# controller.net
KiCad netlist of a schematic drawn in EAGLE
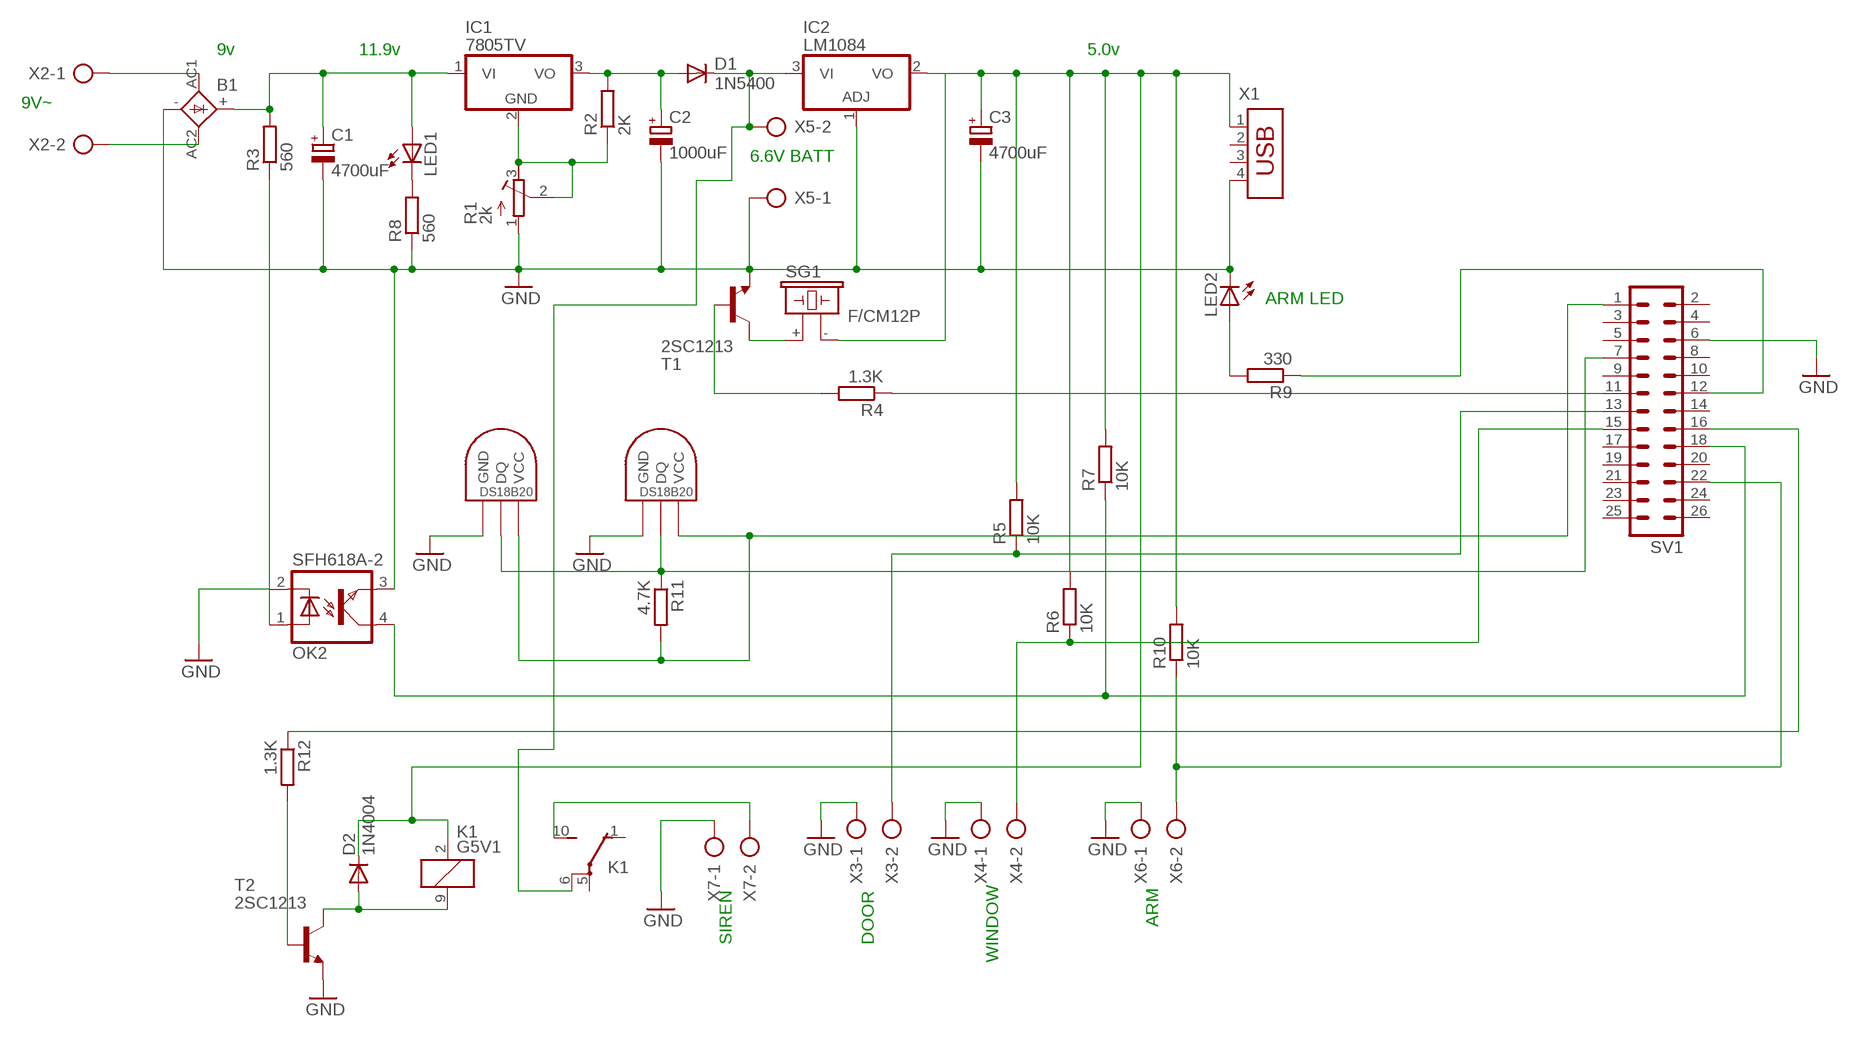
[diagram p0: schematic, sheet 1]

(export (version "E")
  (design (tool "Eeschema 10.0.6"))
  (components
    (comp (ref "B1")
      (value "S41")
      (footprint "eagle-import:S41")
      (libsource (lib "eagle-import") (part "S41"))
    )
    (comp (ref "C1")
      (value "4700uF")
      (footprint "eagle-import:E5-13")
      (libsource (lib "eagle-import") (part "CPOL-EUE5-13"))
    )
    (comp (ref "C2")
      (value "1000uF")
      (footprint "eagle-import:E5-10,5")
      (libsource (lib "eagle-import") (part "CPOL-EUE5-10.5"))
    )
    (comp (ref "C3")
      (value "4700uF")
      (footprint "eagle-import:E5-13")
      (libsource (lib "eagle-import") (part "CPOL-EUE5-13"))
    )
    (comp (ref "D1")
      (value "1N5400")
      (footprint "eagle-import:DO201-15")
      (libsource (lib "eagle-import") (part "1N5400"))
    )
    (comp (ref "D2")
      (value "1N4004")
      (footprint "eagle-import:DO41-10")
      (libsource (lib "eagle-import") (part "1N4004"))
    )
    (comp (ref "IC1")
      (value "7805TV")
      (footprint "eagle-import:TO220V")
      (libsource (lib "eagle-import") (part "78TV05"))
    )
    (comp (ref "IC2")
      (value "LM1084")
      (footprint "eagle-import:TO220V")
      (libsource (lib "eagle-import") (part "MC33269?T-5.0"))
    )
    (comp (ref "K1")
      (value "G5V1")
      (footprint "eagle-import:G5V1")
      (fields (field (name "MPN") "G5V-1-DC24"))
      (libsource (lib "eagle-import") (part "G5V1"))
    )
    (comp (ref "LED1")
      (value "LED5MM")
      (footprint "eagle-import:LED5MM")
      (libsource (lib "eagle-import") (part "LED5MM"))
    )
    (comp (ref "LED2")
      (value "LED5MM")
      (footprint "eagle-import:LED5MM")
      (libsource (lib "eagle-import") (part "LED5MM"))
    )
    (comp (ref "OK2")
      (value "SFH618A-2")
      (footprint "eagle-import:DIP4")
      (fields (field (name "MF") "VISHAY/TELEFUNKEN"))
      (libsource (lib "eagle-import") (part "SFH618?A-2"))
    )
    (comp (ref "R1")
      (value "2k")
      (footprint "eagle-import:RTRIM64W")
      (libsource (lib "eagle-import") (part "R-TRIMM64W"))
    )
    (comp (ref "R2")
      (value "2K")
      (footprint "eagle-import:0204_7")
      (libsource (lib "eagle-import") (part "R-EU_0204/7"))
    )
    (comp (ref "R3")
      (value "560")
      (footprint "eagle-import:0204_7")
      (libsource (lib "eagle-import") (part "R-EU_0204/7"))
    )
    (comp (ref "R4")
      (value "1.3K")
      (footprint "eagle-import:0204_7")
      (libsource (lib "eagle-import") (part "R-EU_0204/7"))
    )
    (comp (ref "R5")
      (value "10K")
      (footprint "eagle-import:0204_7")
      (libsource (lib "eagle-import") (part "R-EU_0204/7"))
    )
    (comp (ref "R6")
      (value "10K")
      (footprint "eagle-import:0204_7")
      (libsource (lib "eagle-import") (part "R-EU_0204/7"))
    )
    (comp (ref "R7")
      (value "10K")
      (footprint "eagle-import:0204_7")
      (libsource (lib "eagle-import") (part "R-EU_0204/7"))
    )
    (comp (ref "R8")
      (value "560")
      (footprint "eagle-import:0204_7")
      (libsource (lib "eagle-import") (part "R-EU_0204/7"))
    )
    (comp (ref "R9")
      (value "330")
      (footprint "eagle-import:0204_7")
      (libsource (lib "eagle-import") (part "R-EU_0204/7"))
    )
    (comp (ref "R10")
      (value "10K")
      (footprint "eagle-import:0204_7")
      (libsource (lib "eagle-import") (part "R-EU_0204/7"))
    )
    (comp (ref "R11")
      (value "4.7K")
      (footprint "eagle-import:0204_7")
      (libsource (lib "eagle-import") (part "R-EU_0204/7"))
    )
    (comp (ref "R12")
      (value "1.3K")
      (footprint "eagle-import:0204_7")
      (libsource (lib "eagle-import") (part "R-EU_0204/7"))
    )
    (comp (ref "SG1")
      (value "F/CM12P")
      (footprint "eagle-import:F_CM12P")
      (libsource (lib "eagle-import") (part "F/CM12P"))
    )
    (comp (ref "SV1")
      (value "ML26L")
      (footprint "eagle-import:ML26L")
      (libsource (lib "eagle-import") (part "ML26L"))
    )
    (comp (ref "T1")
      (value "2SC1213")
      (footprint "eagle-import:TO92-EBC")
      (libsource (lib "eagle-import") (part "-NPN-TO92-EBC"))
    )
    (comp (ref "T2")
      (value "2SC1213")
      (footprint "eagle-import:TO92-EBC")
      (libsource (lib "eagle-import") (part "-NPN-TO92-EBC"))
    )
    (comp (ref "U$1")
      (value "DS1820TO92")
      (footprint "eagle-import:DS1820")
      (libsource (lib "eagle-import") (part "DS1820TO92"))
    )
    (comp (ref "U$2")
      (value "DS1820TO92")
      (footprint "eagle-import:DS1820")
      (libsource (lib "eagle-import") (part "DS1820TO92"))
    )
    (comp (ref "X1")
      (value "USB-787616")
      (footprint "eagle-import:USB")
      (libsource (lib "eagle-import") (part "USB-787616"))
    )
    (comp (ref "X2")
      (value "AK500/2")
      (footprint "eagle-import:AK500_2")
      (libsource (lib "eagle-import") (part "AK500/2"))
    )
    (comp (ref "X3")
      (value "AK500/2")
      (footprint "eagle-import:AK500_2")
      (libsource (lib "eagle-import") (part "AK500/2"))
    )
    (comp (ref "X4")
      (value "AK500/2")
      (footprint "eagle-import:AK500_2")
      (libsource (lib "eagle-import") (part "AK500/2"))
    )
    (comp (ref "X5")
      (value "AK500/2")
      (footprint "eagle-import:AK500_2")
      (libsource (lib "eagle-import") (part "AK500/2"))
    )
    (comp (ref "X6")
      (value "AK500/2")
      (footprint "eagle-import:AK500_2")
      (libsource (lib "eagle-import") (part "AK500/2"))
    )
    (comp (ref "X7")
      (value "AK500/2")
      (footprint "eagle-import:AK500_2")
      (libsource (lib "eagle-import") (part "AK500/2"))
    )
  )
  (nets
    (net (code "1") (name "GND") (class "Default")
      (node (ref "B1") (pin "-") (pinfunction "-_-") (pintype "passive"))
      (node (ref "C1") (pin "-") (pinfunction "-_-") (pintype "passive"))
      (node (ref "C2") (pin "-") (pinfunction "-_-") (pintype "passive"))
      (node (ref "C3") (pin "-") (pinfunction "-_-") (pintype "passive"))
      (node (ref "IC2") (pin "1") (pinfunction "ADJ_1") (pintype "input"))
      (node (ref "LED2") (pin "K") (pinfunction "C_K") (pintype "passive"))
      (node (ref "OK2") (pin "2") (pinfunction "C_2") (pintype "passive"))
      (node (ref "OK2") (pin "3") (pinfunction "EMIT_3") (pintype "passive"))
      (node (ref "R1") (pin "1") (pinfunction "E_1") (pintype "passive"))
      (node (ref "R8") (pin "1") (pinfunction "1_1") (pintype "passive"))
      (node (ref "SV1") (pin "6") (pinfunction "6_6") (pintype "passive"))
      (node (ref "T1") (pin "E") (pinfunction "E_E") (pintype "passive"))
      (node (ref "T2") (pin "E") (pinfunction "E_E") (pintype "passive"))
      (node (ref "U$1") (pin "GND") (pinfunction "GND_GND") (pintype "power_in"))
      (node (ref "U$2") (pin "GND") (pinfunction "GND_GND") (pintype "power_in"))
      (node (ref "X1") (pin "4") (pinfunction "4_4") (pintype "passive"))
      (node (ref "X3") (pin "1") (pinfunction "KL_1") (pintype "passive"))
      (node (ref "X4") (pin "1") (pinfunction "KL_1") (pintype "passive"))
      (node (ref "X5") (pin "1") (pinfunction "KL_1") (pintype "passive"))
      (node (ref "X6") (pin "1") (pinfunction "KL_1") (pintype "passive"))
      (node (ref "X7") (pin "1") (pinfunction "KL_1") (pintype "passive"))
    )
    (net (code "2") (name "Net-(IC1-GND)") (class "Default")
      (node (ref "IC1") (pin "2") (pinfunction "GND_2") (pintype "passive"))
      (node (ref "R1") (pin "2") (pinfunction "S_2") (pintype "passive"))
      (node (ref "R1") (pin "3") (pinfunction "A_3") (pintype "passive"))
      (node (ref "R2") (pin "1") (pinfunction "1_1") (pintype "passive"))
    )
    (net (code "3") (name "Net-(IC1-VI)") (class "Default")
      (node (ref "B1") (pin "+") (pinfunction "+_+") (pintype "passive"))
      (node (ref "C1") (pin "+") (pinfunction "+_+") (pintype "passive"))
      (node (ref "IC1") (pin "1") (pinfunction "VI_1") (pintype "input"))
      (node (ref "LED1") (pin "A") (pinfunction "A_A") (pintype "passive"))
      (node (ref "R3") (pin "2") (pinfunction "2_2") (pintype "passive"))
    )
    (net (code "4") (name "Net-(IC1-VO)") (class "Default")
      (node (ref "C2") (pin "+") (pinfunction "+_+") (pintype "passive"))
      (node (ref "D1") (pin "A") (pinfunction "A_A") (pintype "passive"))
      (node (ref "IC1") (pin "3") (pinfunction "VO_3") (pintype "passive"))
      (node (ref "R2") (pin "2") (pinfunction "2_2") (pintype "passive"))
    )
    (net (code "5") (name "Net-(IC2-VI)") (class "Default")
      (node (ref "D1") (pin "C") (pinfunction "C_C") (pintype "passive"))
      (node (ref "IC2") (pin "3") (pinfunction "VI_3") (pintype "input"))
      (node (ref "K1") (pin "6") (pinfunction "P_6") (pintype "passive"))
      (node (ref "X5") (pin "2") (pinfunction "KL_2") (pintype "passive"))
    )
    (net (code "6") (name "Net-(IC2-VO)") (class "Default")
      (node (ref "C3") (pin "+") (pinfunction "+_+") (pintype "passive"))
      (node (ref "D2") (pin "C") (pinfunction "C_C") (pintype "passive"))
      (node (ref "IC2") (pin "2") (pinfunction "VO_2") (pintype "passive"))
      (node (ref "K1") (pin "2") (pinfunction "1_2") (pintype "passive"))
      (node (ref "R10") (pin "2") (pinfunction "2_2") (pintype "passive"))
      (node (ref "R5") (pin "2") (pinfunction "2_2") (pintype "passive"))
      (node (ref "R6") (pin "2") (pinfunction "2_2") (pintype "passive"))
      (node (ref "R7") (pin "2") (pinfunction "2_2") (pintype "passive"))
      (node (ref "SG1") (pin "-") (pinfunction "2_-") (pintype "passive"))
      (node (ref "X1") (pin "1") (pinfunction "1_1") (pintype "passive"))
    )
    (net (code "7") (name "Net-(K1A-2)") (class "Default")
      (node (ref "D2") (pin "A") (pinfunction "A_A") (pintype "passive"))
      (node (ref "K1") (pin "9") (pinfunction "2_9") (pintype "passive"))
      (node (ref "T2") (pin "C") (pinfunction "C_C") (pintype "passive"))
    )
    (net (code "8") (name "Net-(K1B-S)") (class "Default")
      (node (ref "K1") (pin "10") (pinfunction "S_10") (pintype "passive"))
      (node (ref "X7") (pin "2") (pinfunction "KL_2") (pintype "passive"))
    )
    (net (code "9") (name "Net-(LED1-C)") (class "Default")
      (node (ref "LED1") (pin "K") (pinfunction "C_K") (pintype "passive"))
      (node (ref "R8") (pin "2") (pinfunction "2_2") (pintype "passive"))
    )
    (net (code "10") (name "Net-(LED2-PadA)") (class "Default")
      (node (ref "LED2") (pin "A") (pinfunction "A_A") (pintype "passive"))
      (node (ref "R9") (pin "2") (pinfunction "2_2") (pintype "passive"))
    )
    (net (code "11") (name "Net-(OK2-A)") (class "Default")
      (node (ref "OK2") (pin "1") (pinfunction "A_1") (pintype "passive"))
      (node (ref "R3") (pin "1") (pinfunction "1_1") (pintype "passive"))
    )
    (net (code "12") (name "Net-(OK2-COL)") (class "Default")
      (node (ref "OK2") (pin "4") (pinfunction "COL_4") (pintype "passive"))
      (node (ref "R7") (pin "1") (pinfunction "1_1") (pintype "passive"))
      (node (ref "SV1") (pin "18") (pinfunction "18_18") (pintype "passive"))
    )
    (net (code "13") (name "Net-(R4-Pad1)") (class "Default")
      (node (ref "R4") (pin "1") (pinfunction "1_1") (pintype "passive"))
      (node (ref "SV1") (pin "11") (pinfunction "11_11") (pintype "passive"))
    )
    (net (code "14") (name "Net-(R4-Pad2)") (class "Default")
      (node (ref "R4") (pin "2") (pinfunction "2_2") (pintype "passive"))
      (node (ref "T1") (pin "B") (pinfunction "B_B") (pintype "passive"))
    )
    (net (code "15") (name "Net-(R9-Pad1)") (class "Default")
      (node (ref "R9") (pin "1") (pinfunction "1_1") (pintype "passive"))
      (node (ref "SV1") (pin "12") (pinfunction "12_12") (pintype "passive"))
    )
    (net (code "16") (name "Net-(R11-Pad1)") (class "Default")
      (node (ref "R11") (pin "1") (pinfunction "1_1") (pintype "passive"))
      (node (ref "SV1") (pin "7") (pinfunction "7_7") (pintype "passive"))
      (node (ref "U$1") (pin "DQ") (pinfunction "DQ_DQ") (pintype "bidirectional"))
      (node (ref "U$2") (pin "DQ") (pinfunction "DQ_DQ") (pintype "bidirectional"))
    )
    (net (code "17") (name "Net-(R12-Pad1)") (class "Default")
      (node (ref "R12") (pin "1") (pinfunction "1_1") (pintype "passive"))
      (node (ref "SV1") (pin "16") (pinfunction "16_16") (pintype "passive"))
    )
    (net (code "18") (name "Net-(R12-Pad2)") (class "Default")
      (node (ref "R12") (pin "2") (pinfunction "2_2") (pintype "passive"))
      (node (ref "T2") (pin "B") (pinfunction "B_B") (pintype "passive"))
    )
    (net (code "19") (name "Net-(SG1-1)") (class "Default")
      (node (ref "SG1") (pin "+") (pinfunction "1_+") (pintype "passive"))
      (node (ref "T1") (pin "C") (pinfunction "C_C") (pintype "passive"))
    )
    (net (code "20") (name "Net-(U$1-VCC)") (class "Default")
      (node (ref "R11") (pin "2") (pinfunction "2_2") (pintype "passive"))
      (node (ref "SV1") (pin "1") (pinfunction "1_1") (pintype "passive"))
      (node (ref "U$1") (pin "VDD") (pinfunction "VCC_VDD") (pintype "power_in"))
      (node (ref "U$2") (pin "VDD") (pinfunction "VCC_VDD") (pintype "power_in"))
    )
    (net (code "21") (name "Net-(X2A-KL)") (class "Default")
      (node (ref "B1") (pin "AC1") (pinfunction "AC1_AC1") (pintype "passive"))
      (node (ref "X2") (pin "1") (pinfunction "KL_1") (pintype "passive"))
    )
    (net (code "22") (name "Net-(X2B-KL)") (class "Default")
      (node (ref "B1") (pin "AC2") (pinfunction "AC2_AC2") (pintype "passive"))
      (node (ref "X2") (pin "2") (pinfunction "KL_2") (pintype "passive"))
    )
    (net (code "23") (name "Net-(X3B-KL)") (class "Default")
      (node (ref "R5") (pin "1") (pinfunction "1_1") (pintype "passive"))
      (node (ref "SV1") (pin "13") (pinfunction "13_13") (pintype "passive"))
      (node (ref "X3") (pin "2") (pinfunction "KL_2") (pintype "passive"))
    )
    (net (code "24") (name "Net-(X4B-KL)") (class "Default")
      (node (ref "R6") (pin "1") (pinfunction "1_1") (pintype "passive"))
      (node (ref "SV1") (pin "15") (pinfunction "15_15") (pintype "passive"))
      (node (ref "X4") (pin "2") (pinfunction "KL_2") (pintype "passive"))
    )
    (net (code "25") (name "Net-(X6B-KL)") (class "Default")
      (node (ref "R10") (pin "1") (pinfunction "1_1") (pintype "passive"))
      (node (ref "SV1") (pin "22") (pinfunction "22_22") (pintype "passive"))
      (node (ref "X6") (pin "2") (pinfunction "KL_2") (pintype "passive"))
    )
    (net (code "26") (name "unconnected-(K1B-O-Pad1)") (class "Default")
      (node (ref "K1") (pin "1") (pinfunction "O_1") (pintype "passive"))
    )
    (net (code "27") (name "unconnected-(K1B-P-Pad5)") (class "Default")
      (node (ref "K1") (pin "5") (pinfunction "P_5") (pintype "passive"))
    )
    (net (code "28") (name "unconnected-(SV1-Pad2)") (class "Default")
      (node (ref "SV1") (pin "2") (pinfunction "2_2") (pintype "passive"))
    )
    (net (code "29") (name "unconnected-(SV1-Pad3)") (class "Default")
      (node (ref "SV1") (pin "3") (pinfunction "3_3") (pintype "passive"))
    )
    (net (code "30") (name "unconnected-(SV1-Pad4)") (class "Default")
      (node (ref "SV1") (pin "4") (pinfunction "4_4") (pintype "passive"))
    )
    (net (code "31") (name "unconnected-(SV1-Pad5)") (class "Default")
      (node (ref "SV1") (pin "5") (pinfunction "5_5") (pintype "passive"))
    )
    (net (code "32") (name "unconnected-(SV1-Pad8)") (class "Default")
      (node (ref "SV1") (pin "8") (pinfunction "8_8") (pintype "passive"))
    )
    (net (code "33") (name "unconnected-(SV1-Pad9)") (class "Default")
      (node (ref "SV1") (pin "9") (pinfunction "9_9") (pintype "passive"))
    )
    (net (code "34") (name "unconnected-(SV1-Pad10)") (class "Default")
      (node (ref "SV1") (pin "10") (pinfunction "10_10") (pintype "passive"))
    )
    (net (code "35") (name "unconnected-(SV1-Pad14)") (class "Default")
      (node (ref "SV1") (pin "14") (pinfunction "14_14") (pintype "passive"))
    )
    (net (code "36") (name "unconnected-(SV1-Pad17)") (class "Default")
      (node (ref "SV1") (pin "17") (pinfunction "17_17") (pintype "passive"))
    )
    (net (code "37") (name "unconnected-(SV1-Pad19)") (class "Default")
      (node (ref "SV1") (pin "19") (pinfunction "19_19") (pintype "passive"))
    )
    (net (code "38") (name "unconnected-(SV1-Pad20)") (class "Default")
      (node (ref "SV1") (pin "20") (pinfunction "20_20") (pintype "passive"))
    )
    (net (code "39") (name "unconnected-(SV1-Pad21)") (class "Default")
      (node (ref "SV1") (pin "21") (pinfunction "21_21") (pintype "passive"))
    )
    (net (code "40") (name "unconnected-(SV1-Pad23)") (class "Default")
      (node (ref "SV1") (pin "23") (pinfunction "23_23") (pintype "passive"))
    )
    (net (code "41") (name "unconnected-(SV1-Pad24)") (class "Default")
      (node (ref "SV1") (pin "24") (pinfunction "24_24") (pintype "passive"))
    )
    (net (code "42") (name "unconnected-(SV1-Pad25)") (class "Default")
      (node (ref "SV1") (pin "25") (pinfunction "25_25") (pintype "passive"))
    )
    (net (code "43") (name "unconnected-(SV1-Pad26)") (class "Default")
      (node (ref "SV1") (pin "26") (pinfunction "26_26") (pintype "passive"))
    )
    (net (code "44") (name "unconnected-(X1-Pad2)") (class "Default")
      (node (ref "X1") (pin "2") (pinfunction "2_2") (pintype "passive"))
    )
    (net (code "45") (name "unconnected-(X1-Pad3)") (class "Default")
      (node (ref "X1") (pin "3") (pinfunction "3_3") (pintype "passive"))
    )
  )
)
